# SCH_N64-PSU_2023-12-16.net
KiCad netlist of a schematic drawn in EasyEDA
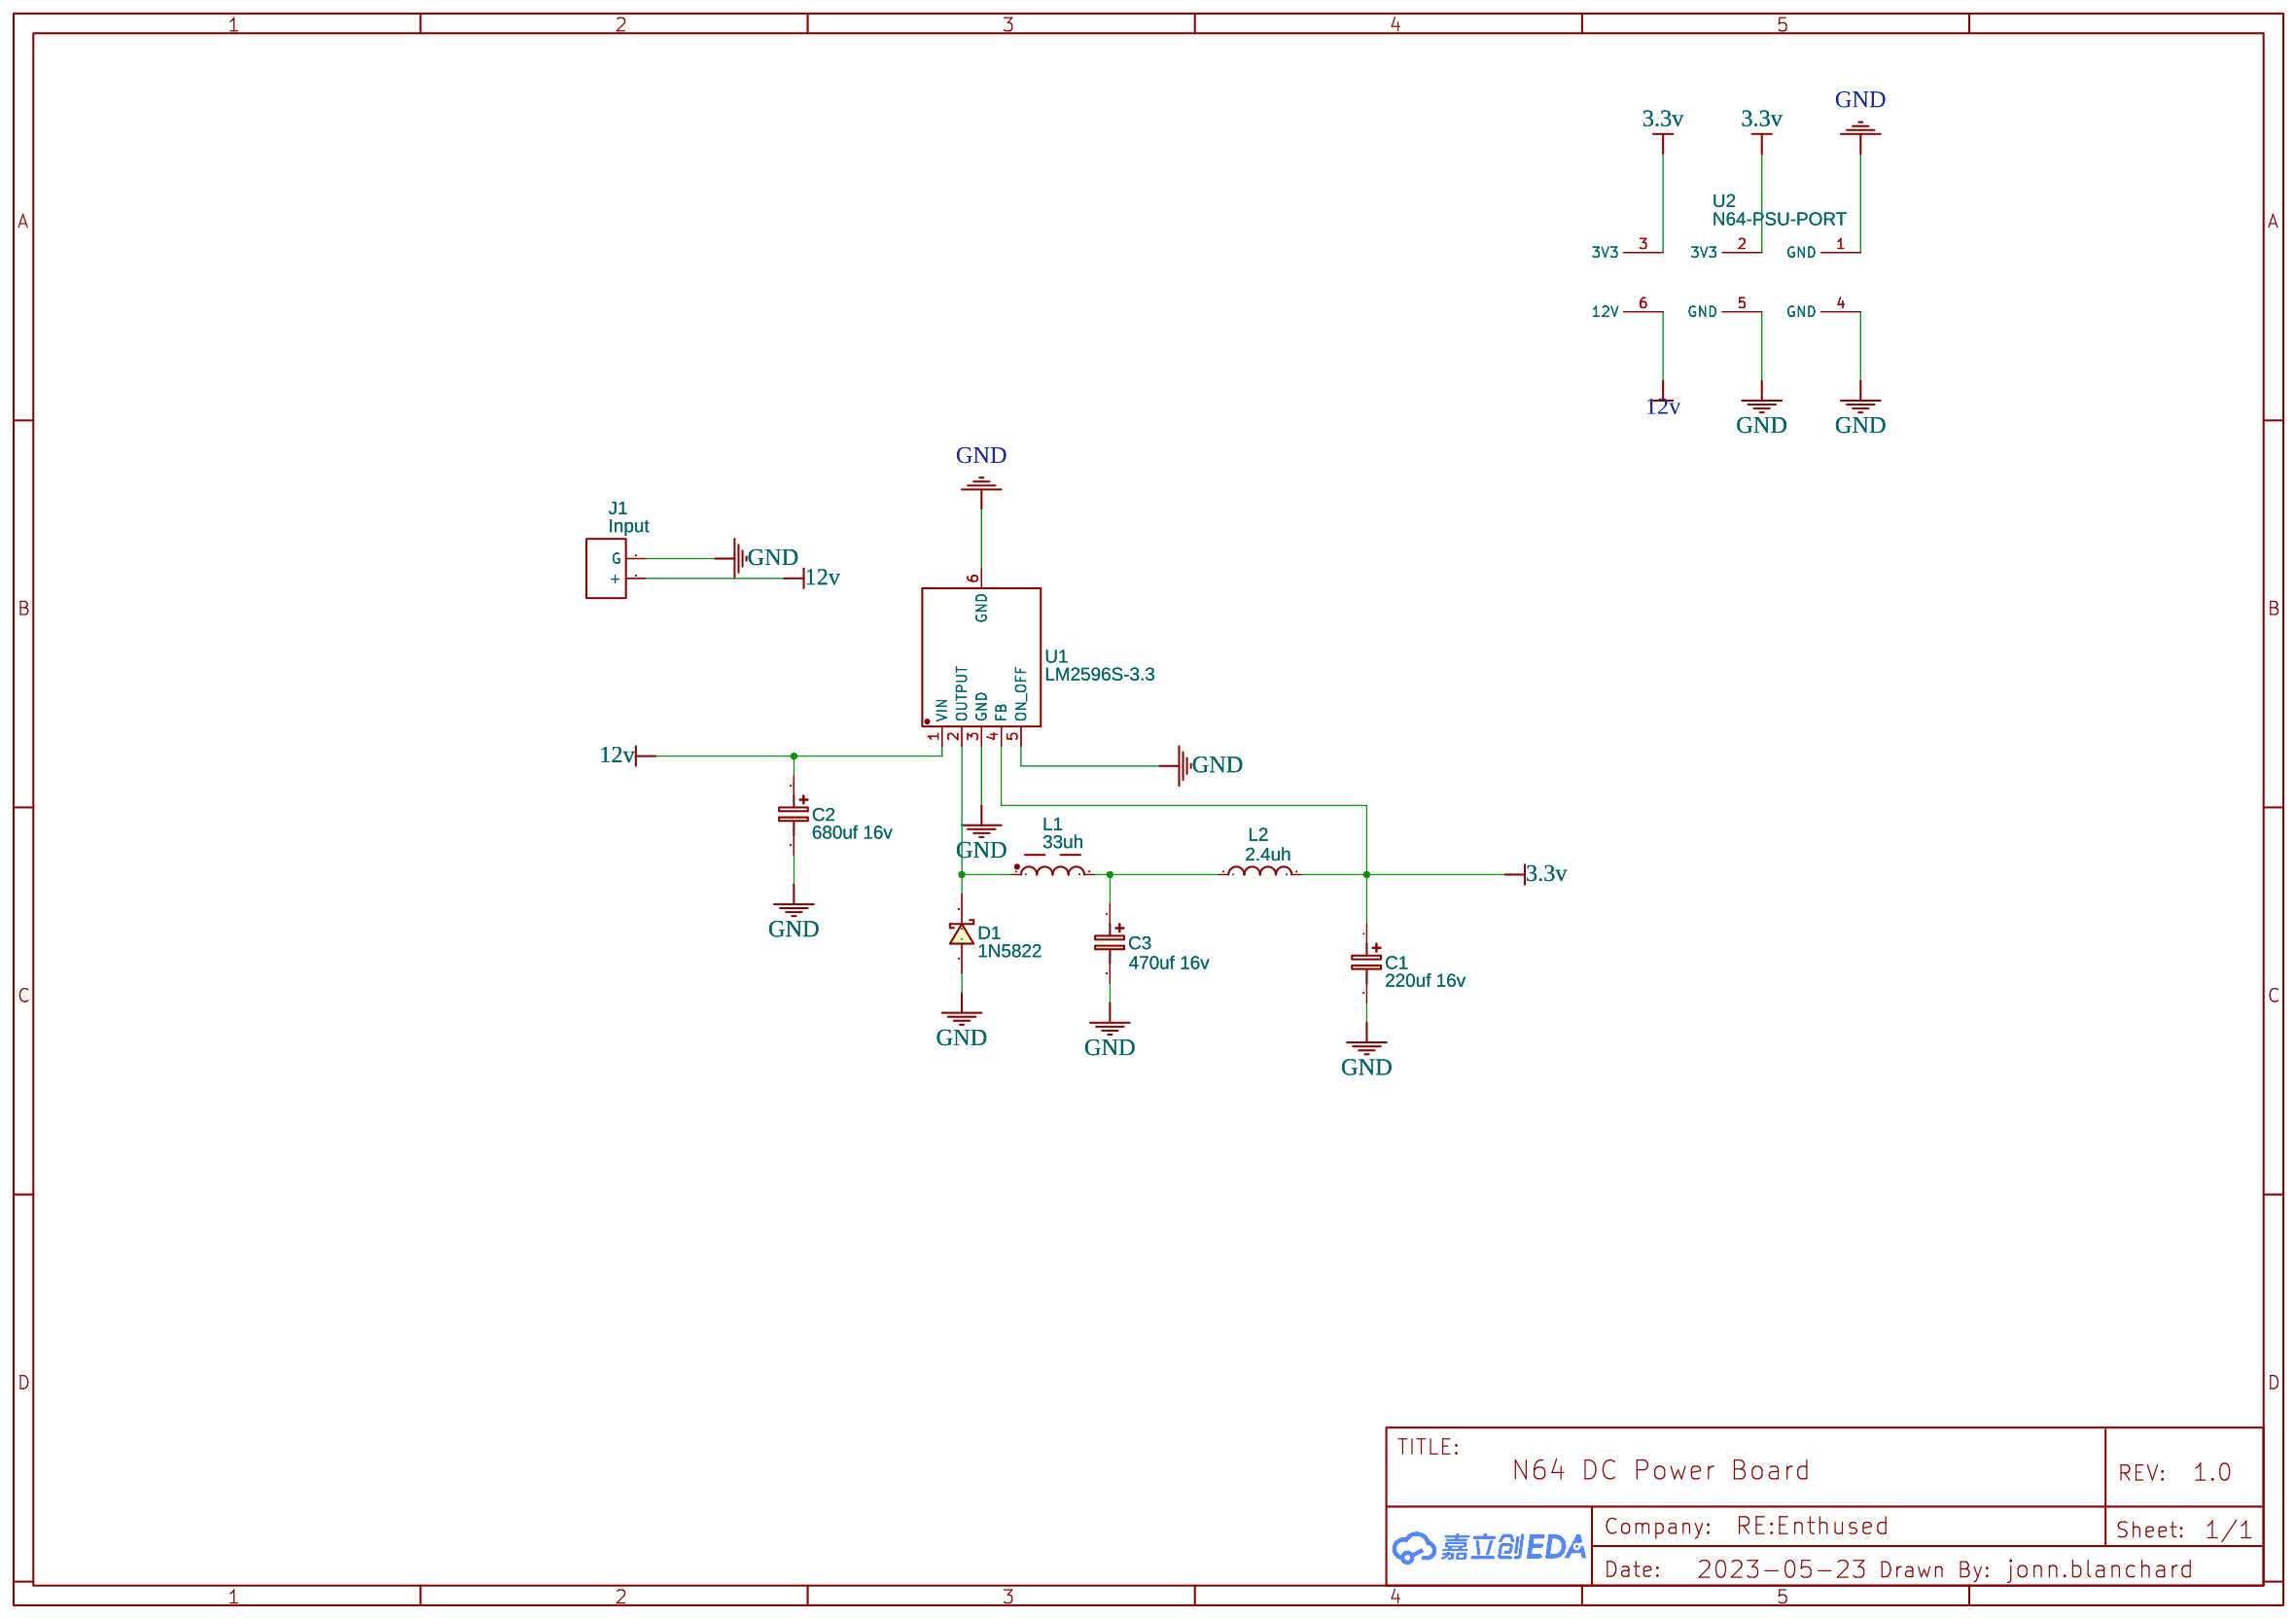
[diagram p0: schematic sheet]

(export (version "E")
  (design (tool "Eeschema 10.0.6"))
  (components
    (comp (ref "C1") (value "220uf 16v") (libsource (lib "") (part "CE_TH_D6.3×F2.5_EU")))
    (comp (ref "C2") (value "680uf 16v") (libsource (lib "") (part "CE_TH_D6.3×F2.5_EU_1")))
    (comp (ref "C3") (value "470uf 16v") (libsource (lib "") (part "CE_TH_D6.3×F2.5_EU")))
    (comp (ref "D1")
      (value "1N5822")
      (fields (field (name "Manufacturer Part") "1N5822-E3/73"))
      (libsource (lib "") (part "1N5822"))
    )
    (comp (ref "J1") (value "Input") (libsource (lib "") (part "HDR-M-2.54_1x2")))
    (comp (ref "L1")
      (value "33uh")
      (fields (field (name "Manufacturer Part") "7447709330") (field (name "Manufacturer") "Wurth Eletronik"))
      (libsource (lib "") (part "FIXED IND 33UH 4.2A 45 MOHM - 1212"))
    )
    (comp (ref "L2")
      (value "2.4uh")
      (fields
        (field (name "Manufacturer Part") "78433490240")
        (field (name "Manufacturer") "Wurth Eletronik")
      )
      (libsource (lib "") (part "WE-CHSA P Performance SMT High Current Inductor - 8090"))
    )
    (comp (ref "U1")
      (value "LM2596S-3.3")
      (fields (field (name "Manufacturer Part") "LM2596S-3.3RG") (field (name "Manufacturer") "HGC(深圳汉芯)"))
      (libsource (lib "") (part "LM2596S-3.3RG_C5189649"))
    )
    (comp (ref "U2") (value "N64-PSU-PORT") (libsource (lib "") (part "N64-PSU-PORT")))
  )
  (nets
    (net (code "1") (name "3.3v") (class "Default")
      (node (ref "C1") (pin "1") (pinfunction "1_1") (pintype "unspecified"))
      (node (ref "L2") (pin "2") (pinfunction "2_2") (pintype "unspecified"))
      (node (ref "U1") (pin "4") (pinfunction "FB_4") (pintype "unspecified"))
      (node (ref "U2") (pin "2") (pinfunction "3V3_2") (pintype "unspecified"))
      (node (ref "U2") (pin "3") (pinfunction "3V3_3") (pintype "unspecified"))
    )
    (net (code "2") (name "12v") (class "Default")
      (node (ref "C2") (pin "1") (pinfunction "1_1") (pintype "unspecified"))
      (node (ref "J1") (pin "1") (pinfunction "+_1") (pintype "unspecified"))
      (node (ref "U1") (pin "1") (pinfunction "VIN_1") (pintype "unspecified"))
      (node (ref "U2") (pin "6") (pinfunction "12V_6") (pintype "unspecified"))
    )
    (net (code "3") (name "GND") (class "Default")
      (node (ref "C1") (pin "2") (pinfunction "2_2") (pintype "unspecified"))
      (node (ref "C2") (pin "2") (pinfunction "2_2") (pintype "unspecified"))
      (node (ref "C3") (pin "2") (pinfunction "2_2") (pintype "unspecified"))
      (node (ref "D1") (pin "1") (pinfunction "A_1") (pintype "unspecified"))
      (node (ref "J1") (pin "2") (pinfunction "G_2") (pintype "unspecified"))
      (node (ref "U1") (pin "3") (pinfunction "GND_3") (pintype "unspecified"))
      (node (ref "U1") (pin "5") (pinfunction "ON_OFF_5") (pintype "unspecified"))
      (node (ref "U1") (pin "6") (pinfunction "GND_6") (pintype "unspecified"))
      (node (ref "U2") (pin "1") (pinfunction "GND_1") (pintype "unspecified"))
      (node (ref "U2") (pin "4") (pinfunction "GND_4") (pintype "unspecified"))
      (node (ref "U2") (pin "5") (pinfunction "GND_5") (pintype "unspecified"))
    )
    (net (code "4") (name "Net-(C3-Pad1)") (class "Default")
      (node (ref "C3") (pin "1") (pinfunction "1_1") (pintype "unspecified"))
      (node (ref "L1") (pin "2") (pinfunction "2_2") (pintype "unspecified"))
      (node (ref "L2") (pin "1") (pinfunction "1_1") (pintype "unspecified"))
    )
    (net (code "5") (name "Net-(D1-K)") (class "Default")
      (node (ref "D1") (pin "2") (pinfunction "K_2") (pintype "unspecified"))
      (node (ref "L1") (pin "1") (pinfunction "1_1") (pintype "unspecified"))
      (node (ref "U1") (pin "2") (pinfunction "OUTPUT_2") (pintype "unspecified"))
    )
  )
)
